# Nixie_Test_3757.net
KiCad netlist of a schematic drawn in EAGLE
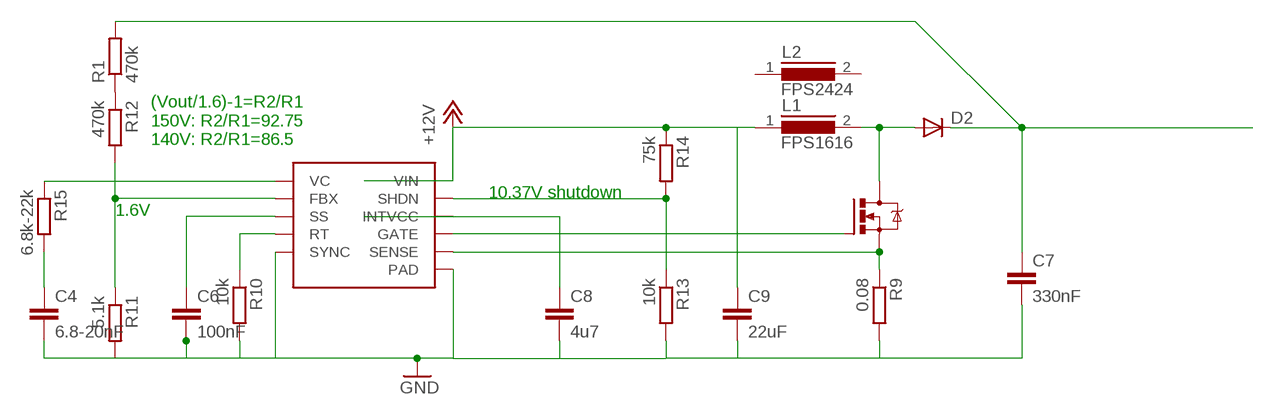
[diagram p0: schematic, sheet 1]

(export (version "E")
  (design (tool "Eeschema 10.0.6"))
  (components
    (comp (ref "C4")
      (value "6.8-20nF")
      (footprint "eagle-import:C0805K")
      (libsource (lib "eagle-import") (part "C-EUC0805K"))
    )
    (comp (ref "C6")
      (value "100nF")
      (footprint "eagle-import:C0805K")
      (libsource (lib "eagle-import") (part "C-EUC0805K"))
    )
    (comp (ref "C7")
      (value "330nF")
      (footprint "eagle-import:C1812")
      (libsource (lib "eagle-import") (part "C-EUC1812"))
    )
    (comp (ref "C8")
      (value "4u7")
      (footprint "eagle-import:C1206K")
      (libsource (lib "eagle-import") (part "C-EUC1206K"))
    )
    (comp (ref "C9")
      (value "22uF")
      (footprint "eagle-import:C1210K")
      (libsource (lib "eagle-import") (part "C-EUC1210K"))
    )
    (comp (ref "D2")
      (value "DIODE-DO219AB")
      (footprint "eagle-import:DO219AB")
      (libsource (lib "eagle-import") (part "DIODE-DO219AB"))
    )
    (comp (ref "L1")
      (value "FPS1616")
      (footprint "eagle-import:1616FPS_22UH")
      (libsource (lib "eagle-import") (part "FPS1616"))
    )
    (comp (ref "L2")
      (value "FPS2424")
      (footprint "eagle-import:242408FPS_22UH")
      (libsource (lib "eagle-import") (part "FPS2424"))
    )
    (comp (ref "Q1")
      (value "N-MOSFET-TO252-DPAK")
      (footprint "eagle-import:TO252")
      (libsource (lib "eagle-import") (part "N-MOSFET-TO252-DPAK"))
    )
    (comp (ref "R1")
      (value "470k")
      (footprint "eagle-import:R0805")
      (libsource (lib "eagle-import") (part "R-EU_R0805"))
    )
    (comp (ref "R9")
      (value "0.08")
      (footprint "eagle-import:R0805")
      (libsource (lib "eagle-import") (part "R-EU_R0805"))
    )
    (comp (ref "R10")
      (value "10k")
      (footprint "eagle-import:R0805")
      (libsource (lib "eagle-import") (part "R-EU_R0805"))
    )
    (comp (ref "R11")
      (value "5.1k")
      (footprint "eagle-import:R0805")
      (libsource (lib "eagle-import") (part "R-EU_R0805"))
    )
    (comp (ref "R12")
      (value "470k")
      (footprint "eagle-import:R0805")
      (libsource (lib "eagle-import") (part "R-EU_R0805"))
    )
    (comp (ref "R13")
      (value "10k")
      (footprint "eagle-import:R0805")
      (libsource (lib "eagle-import") (part "R-EU_R0805"))
    )
    (comp (ref "R14")
      (value "75k")
      (footprint "eagle-import:R0805")
      (libsource (lib "eagle-import") (part "R-EU_R0805"))
    )
    (comp (ref "R15")
      (value "6.8k-22k")
      (footprint "eagle-import:R0805")
      (libsource (lib "eagle-import") (part "R-EU_R0805"))
    )
    (comp (ref "U2")
      (value "LT3757MSOP-10")
      (footprint "eagle-import:MSOP-10")
      (libsource (lib "eagle-import") (part "LT3757MSOP-10"))
    )
  )
  (nets
    (net (code "1") (name "+12V") (class "Default")
      (node (ref "C9") (pin "1") (pinfunction "1_1") (pintype "passive"))
      (node (ref "L1") (pin "1") (pinfunction "1_1") (pintype "passive"))
      (node (ref "R14") (pin "1") (pinfunction "1_1") (pintype "passive"))
      (node (ref "U2") (pin "10") (pinfunction "VIN_10") (pintype "bidirectional"))
    )
    (net (code "2") (name "GND") (class "Default")
      (node (ref "C4") (pin "2") (pinfunction "2_2") (pintype "passive"))
      (node (ref "C6") (pin "2") (pinfunction "2_2") (pintype "passive"))
      (node (ref "C7") (pin "2") (pinfunction "2_2") (pintype "passive"))
      (node (ref "C8") (pin "2") (pinfunction "2_2") (pintype "passive"))
      (node (ref "C9") (pin "2") (pinfunction "2_2") (pintype "passive"))
      (node (ref "R10") (pin "2") (pinfunction "2_2") (pintype "passive"))
      (node (ref "R11") (pin "2") (pinfunction "2_2") (pintype "passive"))
      (node (ref "R13") (pin "2") (pinfunction "2_2") (pintype "passive"))
      (node (ref "R9") (pin "2") (pinfunction "2_2") (pintype "passive"))
      (node (ref "U2") (pin "5") (pinfunction "SYNC_5") (pintype "bidirectional"))
      (node (ref "U2") (pin "PAD") (pinfunction "PAD_PAD") (pintype "bidirectional"))
    )
    (net (code "3") (name "Net-(C4-Pad1)") (class "Default")
      (node (ref "C4") (pin "1") (pinfunction "1_1") (pintype "passive"))
      (node (ref "R15") (pin "2") (pinfunction "2_2") (pintype "passive"))
    )
    (net (code "4") (name "Net-(C7-Pad1)") (class "Default")
      (node (ref "C7") (pin "1") (pinfunction "1_1") (pintype "passive"))
      (node (ref "D2") (pin "C") (pinfunction "C_C") (pintype "passive"))
      (node (ref "R1") (pin "2") (pinfunction "2_2") (pintype "passive"))
    )
    (net (code "5") (name "Net-(Q1-D)") (class "Default")
      (node (ref "D2") (pin "A") (pinfunction "A_A") (pintype "passive"))
      (node (ref "L1") (pin "2") (pinfunction "2_2") (pintype "passive"))
      (node (ref "Q1") (pin "3") (pinfunction "D_3") (pintype "passive"))
    )
    (net (code "6") (name "Net-(Q1-G)") (class "Default")
      (node (ref "Q1") (pin "1") (pinfunction "G_1") (pintype "passive"))
      (node (ref "U2") (pin "7") (pinfunction "GATE_7") (pintype "bidirectional"))
    )
    (net (code "7") (name "Net-(Q1-S)") (class "Default")
      (node (ref "Q1") (pin "2") (pinfunction "S_2") (pintype "passive"))
      (node (ref "R9") (pin "1") (pinfunction "1_1") (pintype "passive"))
      (node (ref "U2") (pin "6") (pinfunction "SENSE_6") (pintype "bidirectional"))
    )
    (net (code "8") (name "Net-(R1-Pad1)") (class "Default")
      (node (ref "R1") (pin "1") (pinfunction "1_1") (pintype "passive"))
      (node (ref "R12") (pin "1") (pinfunction "1_1") (pintype "passive"))
    )
    (net (code "9") (name "Net-(U2-FBX)") (class "Default")
      (node (ref "R11") (pin "1") (pinfunction "1_1") (pintype "passive"))
      (node (ref "R12") (pin "2") (pinfunction "2_2") (pintype "passive"))
      (node (ref "U2") (pin "2") (pinfunction "FBX_2") (pintype "bidirectional"))
    )
    (net (code "10") (name "Net-(U2-INTVCC)") (class "Default")
      (node (ref "C8") (pin "1") (pinfunction "1_1") (pintype "passive"))
      (node (ref "U2") (pin "8") (pinfunction "INTVCC_8") (pintype "bidirectional"))
    )
    (net (code "11") (name "Net-(U2-RT)") (class "Default")
      (node (ref "R10") (pin "1") (pinfunction "1_1") (pintype "passive"))
      (node (ref "U2") (pin "4") (pinfunction "RT_4") (pintype "bidirectional"))
    )
    (net (code "12") (name "Net-(U2-SHDN)") (class "Default")
      (node (ref "R13") (pin "1") (pinfunction "1_1") (pintype "passive"))
      (node (ref "R14") (pin "2") (pinfunction "2_2") (pintype "passive"))
      (node (ref "U2") (pin "9") (pinfunction "SHDN_9") (pintype "bidirectional"))
    )
    (net (code "13") (name "Net-(U2-SS)") (class "Default")
      (node (ref "C6") (pin "1") (pinfunction "1_1") (pintype "passive"))
      (node (ref "U2") (pin "3") (pinfunction "SS_3") (pintype "bidirectional"))
    )
    (net (code "14") (name "Net-(U2-VC)") (class "Default")
      (node (ref "R15") (pin "1") (pinfunction "1_1") (pintype "passive"))
      (node (ref "U2") (pin "1") (pinfunction "VC_1") (pintype "bidirectional"))
    )
    (net (code "15") (name "unconnected-(L2-Pad1)") (class "Default")
      (node (ref "L2") (pin "1") (pinfunction "1_1") (pintype "passive"))
    )
    (net (code "16") (name "unconnected-(L2-Pad2)") (class "Default")
      (node (ref "L2") (pin "2") (pinfunction "2_2") (pintype "passive"))
    )
  )
)
